# 3_RF.net
KiCad netlist of a schematic drawn in Altium Designer
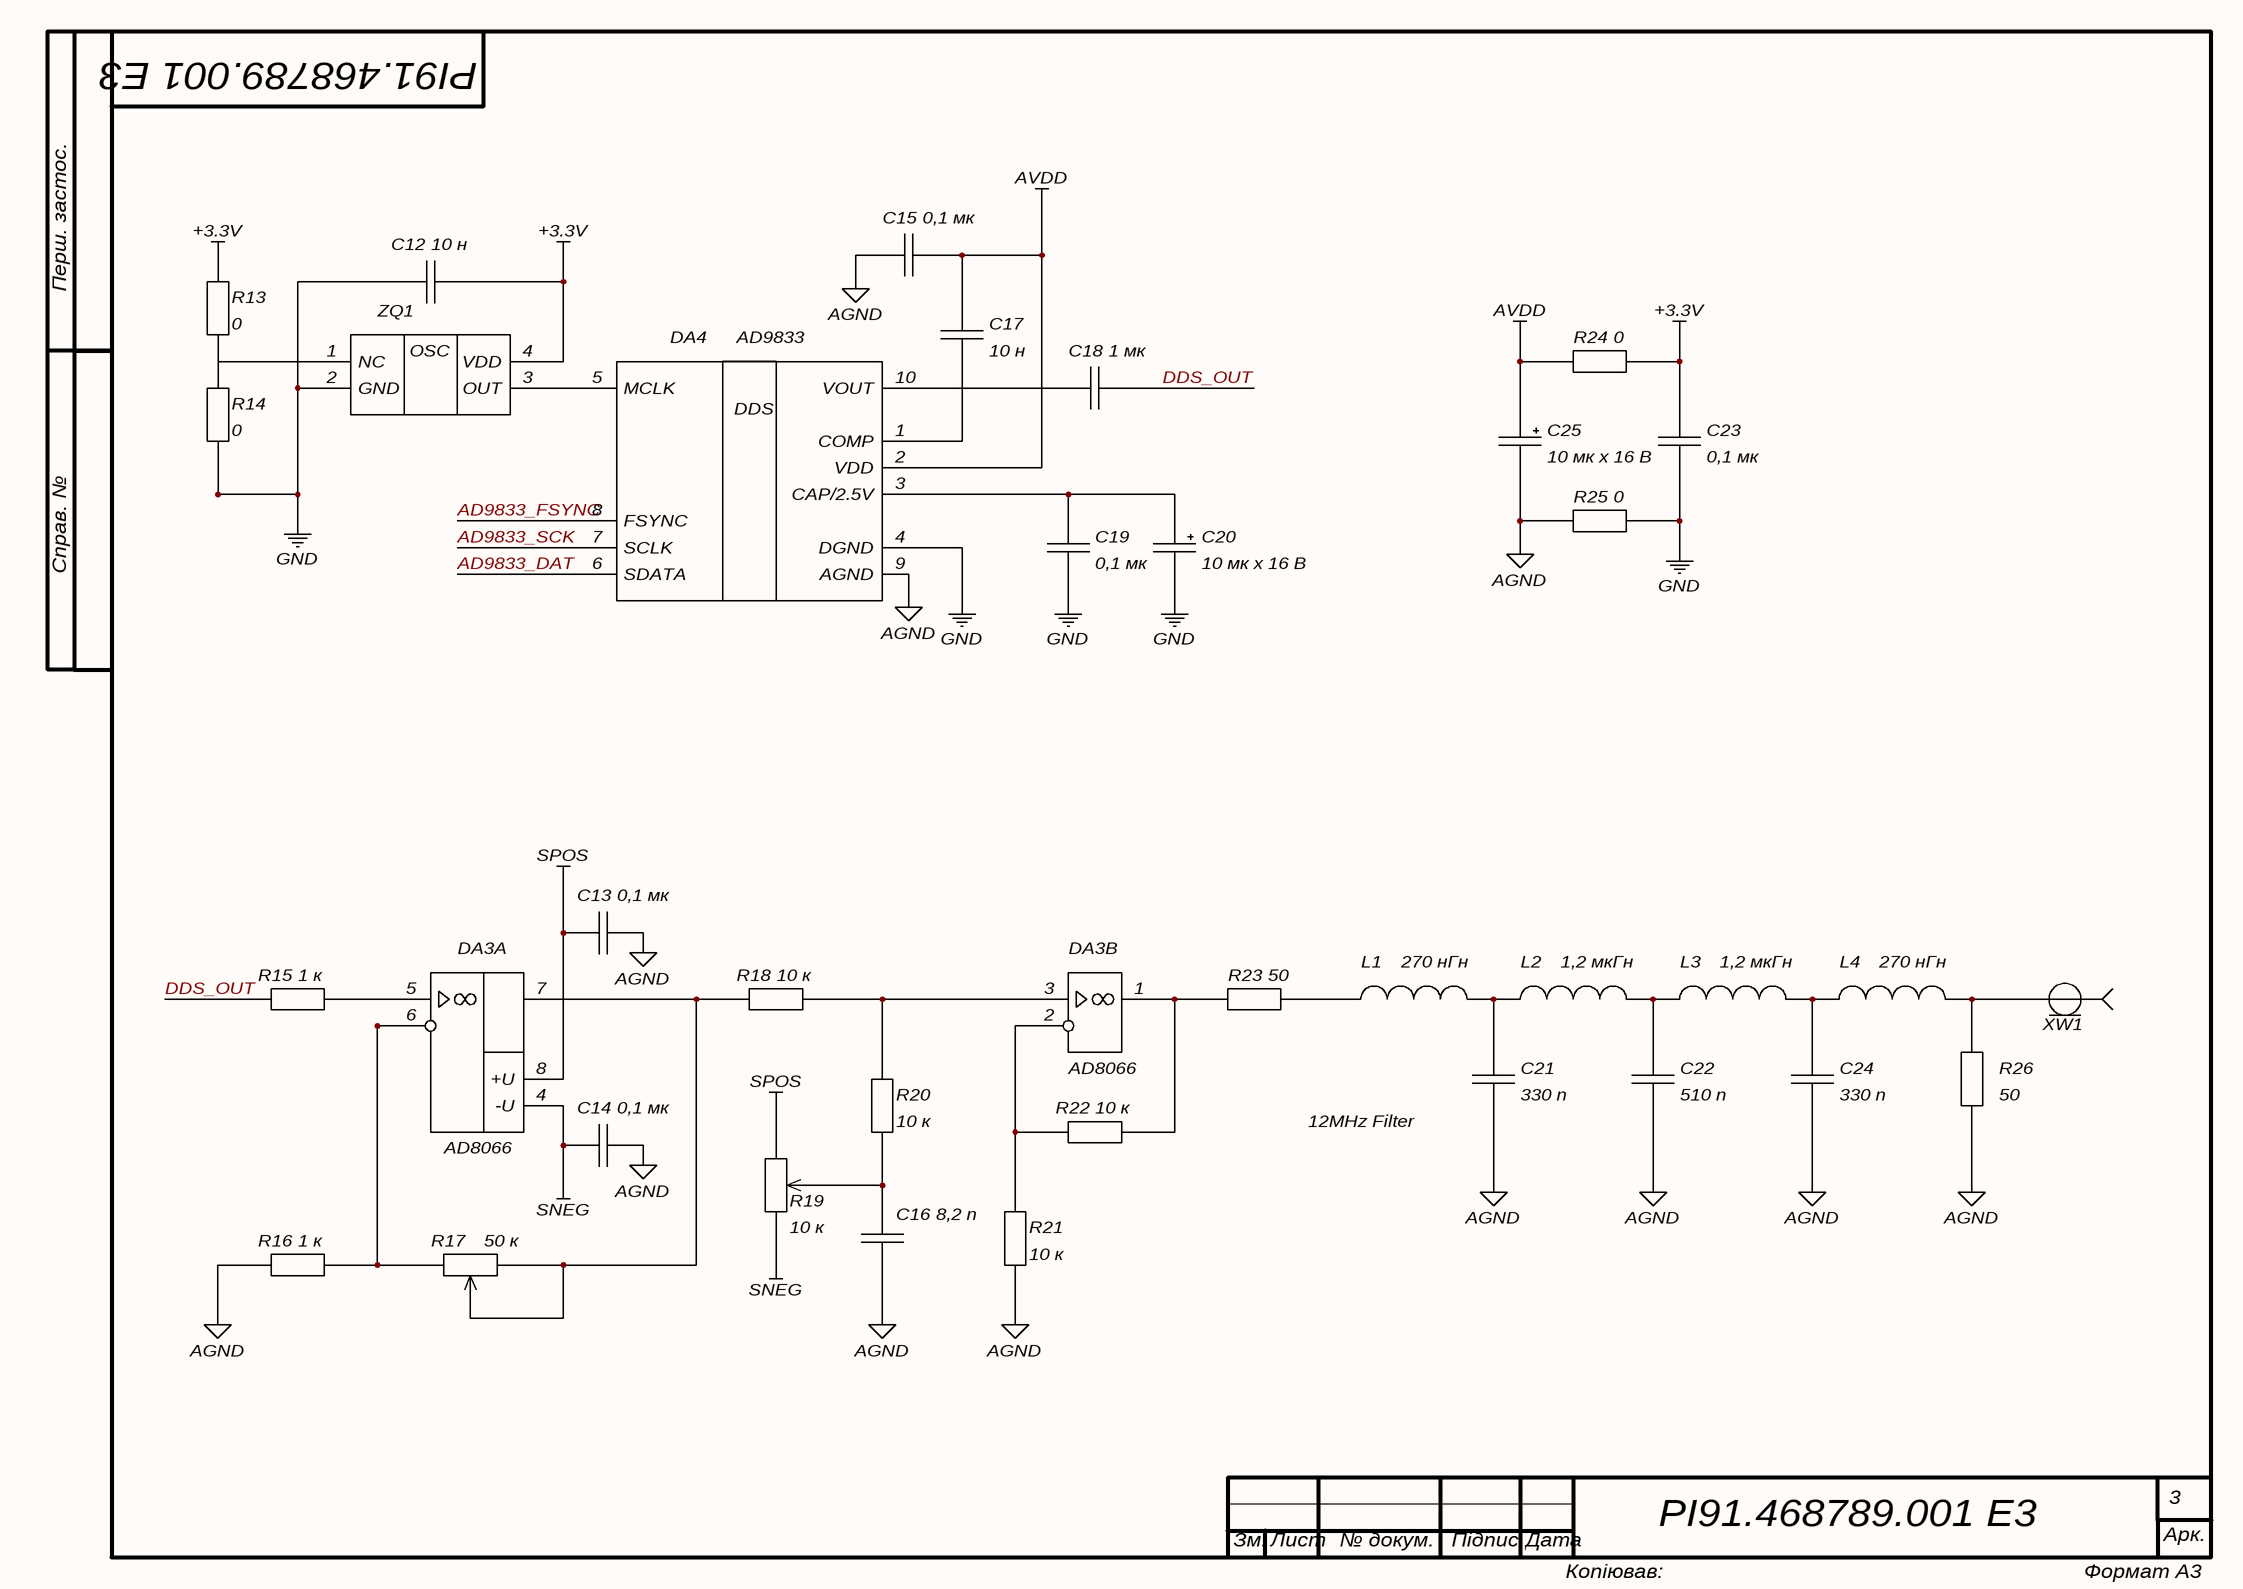
[diagram p0: 3_RF.SchDoc]

(export (version "E")
  (design (tool "Eeschema 10.0.6"))
  (components
    (comp (ref "C12")
      (value "10n")
      (footprint "CAP: 0603")
      (description "Non-polarity")
      (fields (field (name "10 Н") "10 н"))
      (libsource (lib "DDS_Generator") (part "Capacitor"))
    )
    (comp (ref "C13")
      (value "0.1u")
      (footprint "CAP: 0603")
      (description "Non-polarity")
      (fields (field (name "0,1 МК") "0,1 мк"))
      (libsource (lib "DDS_Generator") (part "Capacitor"))
    )
    (comp (ref "C14")
      (value "0.1u")
      (footprint "CAP: 0603")
      (description "Non-polarity")
      (fields (field (name "0,1 МК") "0,1 мк"))
      (libsource (lib "DDS_Generator") (part "Capacitor"))
    )
    (comp (ref "C15")
      (value "0.1u")
      (footprint "CAP: 0603")
      (description "Non-polarity")
      (fields (field (name "0,1 МК") "0,1 мк"))
      (libsource (lib "DDS_Generator") (part "Capacitor"))
    )
    (comp (ref "C16")
      (value "8.2p")
      (footprint "CAP: 0603")
      (description "Non-polarity")
      (fields (field (name "8,2 П") "8,2 п"))
      (libsource (lib "DDS_Generator") (part "Capacitor"))
    )
    (comp (ref "C17")
      (value "10n")
      (footprint "CAP: 0603")
      (description "Non-polarity")
      (fields (field (name "10 Н") "10 н"))
      (libsource (lib "DDS_Generator") (part "Capacitor"))
    )
    (comp (ref "C18")
      (value "1u 50V")
      (footprint "CAP: 0805")
      (description "Non-polarity")
      (fields (field (name "1 МК") "1 мк"))
      (libsource (lib "DDS_Generator") (part "Capacitor"))
    )
    (comp (ref "C19")
      (value "0.1u")
      (footprint "CAP: 0603")
      (description "Non-polarity")
      (fields (field (name "0,1 МК") "0,1 мк"))
      (libsource (lib "DDS_Generator") (part "Capacitor"))
    )
    (comp (ref "C20")
      (value "10u 16V")
      (footprint "CAP: TANTAL-A")
      (description "Polarity")
      (fields (field (name "10 16") "10 мк х 16 В"))
      (libsource (lib "DDS_Generator") (part "Capacitor_polar"))
    )
    (comp (ref "C21")
      (value "330p")
      (footprint "CAP: 0805")
      (description "Non-polarity")
      (fields (field (name "330 П") "330 п"))
      (libsource (lib "DDS_Generator") (part "Capacitor"))
    )
    (comp (ref "C22")
      (value "510p")
      (footprint "CAP: 0805")
      (description "Non-polarity")
      (fields (field (name "510 П") "510 п"))
      (libsource (lib "DDS_Generator") (part "Capacitor"))
    )
    (comp (ref "C23")
      (value "0.1u")
      (footprint "CAP: 0603")
      (description "Non-polarity")
      (fields (field (name "0,1 МК") "0,1 мк"))
      (libsource (lib "DDS_Generator") (part "Capacitor"))
    )
    (comp (ref "C24")
      (value "330p")
      (footprint "CAP: 0805")
      (description "Non-polarity")
      (fields (field (name "330 П") "330 п"))
      (libsource (lib "DDS_Generator") (part "Capacitor"))
    )
    (comp (ref "C25")
      (value "10u 16V")
      (footprint "CAP: TANTAL-A")
      (description "Polarity")
      (fields (field (name "10 16") "10 мк х 16 В"))
      (libsource (lib "DDS_Generator") (part "Capacitor_polar"))
    )
    (comp (ref "DA3")
      (value "AD8066")
      (footprint "8-SOIC")
      (fields (field (name "AD8066") "AD8066"))
      (libsource (lib "DDS_Generator") (part "Op Amp"))
    )
    (comp (ref "DA4")
      (value "AD9833")
      (footprint "10-MSOP")
      (description "DDS Generator")
      (libsource (lib "DDS_Generator") (part "AD9833"))
    )
    (comp (ref "L1")
      (value "270nH")
      (footprint "IND: 0805")
      (fields (field (name "270N") "270 нГн"))
      (libsource (lib "DDS_Generator") (part "Inductor"))
    )
    (comp (ref "L2")
      (value "1.2uH")
      (footprint "IND: 0805")
      (fields (field (name "1.2") "1,2 мкГн"))
      (libsource (lib "DDS_Generator") (part "Inductor"))
    )
    (comp (ref "L3")
      (value "1.2uH")
      (footprint "IND: 0805")
      (fields (field (name "1.2") "1,2 мкГн"))
      (libsource (lib "DDS_Generator") (part "Inductor"))
    )
    (comp (ref "L4")
      (value "270nH")
      (footprint "IND: 0805")
      (fields (field (name "270N") "270 нГн"))
      (libsource (lib "DDS_Generator") (part "Inductor"))
    )
    (comp (ref "R13")
      (value "0")
      (footprint "RES: 0603")
      (fields (field (name "0") "0"))
      (libsource (lib "") (part "Resistor_2"))
    )
    (comp (ref "R14")
      (value "0")
      (footprint "RES: 0603")
      (fields (field (name "0") "0"))
      (libsource (lib "") (part "Resistor_2"))
    )
    (comp (ref "R15")
      (value "1k")
      (footprint "RES: 0805")
      (fields (field (name "1 К") "1 к"))
      (libsource (lib "DDS_Generator") (part "Resistor"))
    )
    (comp (ref "R16")
      (value "1k")
      (footprint "RES: 0805")
      (fields (field (name "1 К") "1 к"))
      (libsource (lib "DDS_Generator") (part "Resistor"))
    )
    (comp (ref "R17")
      (value "10k")
      (footprint "RES: PTV09A-4015F")
      (fields (field (name "50") "50 к"))
      (libsource (lib "") (part "Potentiometer_1"))
    )
    (comp (ref "R18")
      (value "10k")
      (footprint "RES: 0805")
      (fields (field (name "10 К") "10 к"))
      (libsource (lib "DDS_Generator") (part "Resistor"))
    )
    (comp (ref "R19")
      (value "10k")
      (footprint "RES: PTV09A-4015F")
      (fields (field (name "10") "10 к"))
      (libsource (lib "DDS_Generator") (part "Potentiometer"))
    )
    (comp (ref "R20")
      (value "10k")
      (footprint "RES: 0805")
      (fields (field (name "10 К") "10 к"))
      (libsource (lib "") (part "Resistor_2"))
    )
    (comp (ref "R21")
      (value "10k")
      (footprint "RES: 0805")
      (fields (field (name "10 К") "10 к"))
      (libsource (lib "") (part "Resistor_2"))
    )
    (comp (ref "R22")
      (value "10k")
      (footprint "RES: 0805")
      (fields (field (name "10 К") "10 к"))
      (libsource (lib "") (part "Resistor_1"))
    )
    (comp (ref "R23")
      (value "50")
      (footprint "RES: 0805")
      (fields (field (name "50") "50"))
      (libsource (lib "") (part "Resistor_1"))
    )
    (comp (ref "R24")
      (value "0")
      (footprint "RES: 0603")
      (fields (field (name "0") "0"))
      (libsource (lib "") (part "Resistor_1"))
    )
    (comp (ref "R25")
      (value "0")
      (footprint "RES: 0603")
      (fields (field (name "0") "0"))
      (libsource (lib "") (part "Resistor_1"))
    )
    (comp (ref "R26")
      (value "50")
      (footprint "RES: 0805")
      (fields (field (name "50") "50"))
      (libsource (lib "") (part "Resistor_2"))
    )
    (comp (ref "XW1")
      (value "SMA Edge")
      (footprint "CON: SMA EDGE MOUNT")
      (libsource (lib "DDS_Generator") (part "Connector RF"))
    )
    (comp (ref "ZQ1")
      (value "25 MHz")
      (footprint "OSC: 5070G")
      (libsource (lib "DDS_Generator") (part "Oscillator"))
    )
  )
  (nets
    (net (code "1") (name "+3.3V") (class "Default")
      (node (ref "C12") (pin "2") (pinfunction "2_2") (pintype "passive"))
      (node (ref "C23") (pin "2") (pinfunction "2_2") (pintype "passive"))
      (node (ref "R13") (pin "2") (pinfunction "2_2") (pintype "passive"))
      (node (ref "R24") (pin "1") (pinfunction "1_1") (pintype "passive"))
      (node (ref "ZQ1") (pin "4") (pinfunction "VDD_4") (pintype "power_in"))
    )
    (net (code "2") (name "/AD9833_DAT") (class "Default")
      (node (ref "DA4") (pin "6") (pinfunction "SDATA_6") (pintype "passive"))
    )
    (net (code "3") (name "/AD9833_FSYNC") (class "Default")
      (node (ref "DA4") (pin "8") (pinfunction "FSYNC_8") (pintype "passive"))
    )
    (net (code "4") (name "/AD9833_SCK") (class "Default")
      (node (ref "DA4") (pin "7") (pinfunction "SCLK_7") (pintype "passive"))
    )
    (net (code "5") (name "/DDS_OUT") (class "Default")
      (node (ref "C18") (pin "2") (pinfunction "2_2") (pintype "passive"))
      (node (ref "R15") (pin "1") (pinfunction "1_1") (pintype "passive"))
    )
    (net (code "6") (name "AGND") (class "Default")
      (node (ref "C13") (pin "2") (pinfunction "2_2") (pintype "passive"))
      (node (ref "C14") (pin "2") (pinfunction "2_2") (pintype "passive"))
      (node (ref "C15") (pin "2") (pinfunction "2_2") (pintype "passive"))
      (node (ref "C16") (pin "1") (pinfunction "1_1") (pintype "passive"))
      (node (ref "C21") (pin "1") (pinfunction "1_1") (pintype "passive"))
      (node (ref "C22") (pin "1") (pinfunction "1_1") (pintype "passive"))
      (node (ref "C24") (pin "1") (pinfunction "1_1") (pintype "passive"))
      (node (ref "C25") (pin "2") (pinfunction "2_2") (pintype "passive"))
      (node (ref "DA4") (pin "9") (pinfunction "AGND_9") (pintype "power_in"))
      (node (ref "R16") (pin "1") (pinfunction "1_1") (pintype "passive"))
      (node (ref "R21") (pin "1") (pinfunction "1_1") (pintype "passive"))
      (node (ref "R25") (pin "2") (pinfunction "2_2") (pintype "passive"))
      (node (ref "R26") (pin "1") (pinfunction "1_1") (pintype "passive"))
    )
    (net (code "7") (name "AVDD") (class "Default")
      (node (ref "C15") (pin "1") (pinfunction "1_1") (pintype "passive"))
      (node (ref "C17") (pin "1") (pinfunction "1_1") (pintype "passive"))
      (node (ref "C25") (pin "1") (pinfunction "1_1") (pintype "passive"))
      (node (ref "DA4") (pin "2") (pinfunction "VDD_2") (pintype "power_in"))
      (node (ref "R24") (pin "2") (pinfunction "2_2") (pintype "passive"))
    )
    (net (code "8") (name "GND") (class "Default")
      (node (ref "C12") (pin "1") (pinfunction "1_1") (pintype "passive"))
      (node (ref "C19") (pin "1") (pinfunction "1_1") (pintype "passive"))
      (node (ref "C20") (pin "2") (pinfunction "2_2") (pintype "passive"))
      (node (ref "C23") (pin "1") (pinfunction "1_1") (pintype "passive"))
      (node (ref "DA4") (pin "4") (pinfunction "DGND_4") (pintype "power_in"))
      (node (ref "R14") (pin "1") (pinfunction "1_1") (pintype "passive"))
      (node (ref "R25") (pin "1") (pinfunction "1_1") (pintype "passive"))
      (node (ref "ZQ1") (pin "2") (pinfunction "GND_2") (pintype "power_in"))
    )
    (net (code "9") (name "Net-(C16-Pad2)") (class "Default")
      (node (ref "C16") (pin "2") (pinfunction "2_2") (pintype "passive"))
      (node (ref "R19") (pin "2") (pinfunction "3_2") (pintype "passive"))
      (node (ref "R20") (pin "1") (pinfunction "1_1") (pintype "passive"))
    )
    (net (code "10") (name "Net-(C21-Pad2)") (class "Default")
      (node (ref "C21") (pin "2") (pinfunction "2_2") (pintype "passive"))
      (node (ref "L1") (pin "2") (pinfunction "2_2") (pintype "passive"))
      (node (ref "L2") (pin "1") (pinfunction "1_1") (pintype "passive"))
    )
    (net (code "11") (name "Net-(C22-Pad2)") (class "Default")
      (node (ref "C22") (pin "2") (pinfunction "2_2") (pintype "passive"))
      (node (ref "L2") (pin "2") (pinfunction "2_2") (pintype "passive"))
      (node (ref "L3") (pin "1") (pinfunction "1_1") (pintype "passive"))
    )
    (net (code "12") (name "Net-(C24-Pad2)") (class "Default")
      (node (ref "C24") (pin "2") (pinfunction "2_2") (pintype "passive"))
      (node (ref "L3") (pin "2") (pinfunction "2_2") (pintype "passive"))
      (node (ref "L4") (pin "1") (pinfunction "1_1") (pintype "passive"))
    )
    (net (code "13") (name "Net-(DA3A-+IN1)") (class "Default")
      (node (ref "DA3") (pin "5") (pinfunction "+IN1_5") (pintype "passive"))
      (node (ref "R15") (pin "2") (pinfunction "2_2") (pintype "passive"))
    )
    (net (code "14") (name "Net-(DA3A--IN1)") (class "Default")
      (node (ref "DA3") (pin "6") (pinfunction "-IN1_6") (pintype "passive"))
      (node (ref "R16") (pin "2") (pinfunction "2_2") (pintype "passive"))
      (node (ref "R17") (pin "3") (pinfunction "3_3") (pintype "passive"))
    )
    (net (code "15") (name "Net-(DA3A-OUT1)") (class "Default")
      (node (ref "DA3") (pin "7") (pinfunction "OUT1_7") (pintype "passive"))
      (node (ref "R17") (pin "1") (pinfunction "1_1") (pintype "passive"))
      (node (ref "R17") (pin "2") (pinfunction "3_2") (pintype "passive"))
      (node (ref "R18") (pin "1") (pinfunction "1_1") (pintype "passive"))
    )
    (net (code "16") (name "Net-(DA3B-+IN2)") (class "Default")
      (node (ref "DA3") (pin "3") (pinfunction "+IN2_3") (pintype "passive"))
      (node (ref "R18") (pin "2") (pinfunction "2_2") (pintype "passive"))
      (node (ref "R20") (pin "2") (pinfunction "2_2") (pintype "passive"))
    )
    (net (code "17") (name "Net-(DA3B--IN2)") (class "Default")
      (node (ref "DA3") (pin "2") (pinfunction "-IN2_2") (pintype "passive"))
      (node (ref "R21") (pin "2") (pinfunction "2_2") (pintype "passive"))
      (node (ref "R22") (pin "2") (pinfunction "2_2") (pintype "passive"))
    )
    (net (code "18") (name "Net-(DA3B-OUT2)") (class "Default")
      (node (ref "DA3") (pin "1") (pinfunction "OUT2_1") (pintype "passive"))
      (node (ref "R22") (pin "1") (pinfunction "1_1") (pintype "passive"))
      (node (ref "R23") (pin "2") (pinfunction "2_2") (pintype "passive"))
    )
    (net (code "19") (name "Net-(DA4-CAP{slash}2.5V)") (class "Default")
      (node (ref "C19") (pin "2") (pinfunction "2_2") (pintype "passive"))
      (node (ref "C20") (pin "1") (pinfunction "1_1") (pintype "passive"))
      (node (ref "DA4") (pin "3") (pinfunction "CAP/2.5V_3") (pintype "passive"))
    )
    (net (code "20") (name "Net-(DA4-COMP)") (class "Default")
      (node (ref "C17") (pin "2") (pinfunction "2_2") (pintype "passive"))
      (node (ref "DA4") (pin "1") (pinfunction "COMP_1") (pintype "passive"))
    )
    (net (code "21") (name "Net-(DA4-MCLK)") (class "Default")
      (node (ref "DA4") (pin "5") (pinfunction "MCLK_5") (pintype "passive"))
      (node (ref "ZQ1") (pin "3") (pinfunction "OUT_3") (pintype "passive"))
    )
    (net (code "22") (name "Net-(DA4-VOUT)") (class "Default")
      (node (ref "C18") (pin "1") (pinfunction "1_1") (pintype "passive"))
      (node (ref "DA4") (pin "10") (pinfunction "VOUT_10") (pintype "passive"))
    )
    (net (code "23") (name "Net-(L1-Pad1)") (class "Default")
      (node (ref "L1") (pin "1") (pinfunction "1_1") (pintype "passive"))
      (node (ref "R23") (pin "1") (pinfunction "1_1") (pintype "passive"))
    )
    (net (code "24") (name "Net-(XW1-SIG)") (class "Default")
      (node (ref "L4") (pin "2") (pinfunction "2_2") (pintype "passive"))
      (node (ref "R26") (pin "2") (pinfunction "2_2") (pintype "passive"))
      (node (ref "XW1") (pin "1") (pinfunction "SIG_1") (pintype "passive"))
    )
    (net (code "25") (name "Net-(ZQ1-NC)") (class "Default")
      (node (ref "R13") (pin "1") (pinfunction "1_1") (pintype "passive"))
      (node (ref "R14") (pin "2") (pinfunction "2_2") (pintype "passive"))
      (node (ref "ZQ1") (pin "1") (pinfunction "NC_1") (pintype "passive"))
    )
    (net (code "26") (name "SNEG") (class "Default")
      (node (ref "C14") (pin "1") (pinfunction "1_1") (pintype "passive"))
      (node (ref "DA3") (pin "4") (pinfunction "-U_4") (pintype "passive"))
      (node (ref "R19") (pin "3") (pinfunction "3_3") (pintype "passive"))
    )
    (net (code "27") (name "SPOS") (class "Default")
      (node (ref "C13") (pin "1") (pinfunction "1_1") (pintype "passive"))
      (node (ref "DA3") (pin "8") (pinfunction "+U_8") (pintype "passive"))
      (node (ref "R19") (pin "1") (pinfunction "1_1") (pintype "passive"))
    )
  )
)
